# 425AK01A_S09.net
KiCad netlist of a schematic drawn in Altium Designer
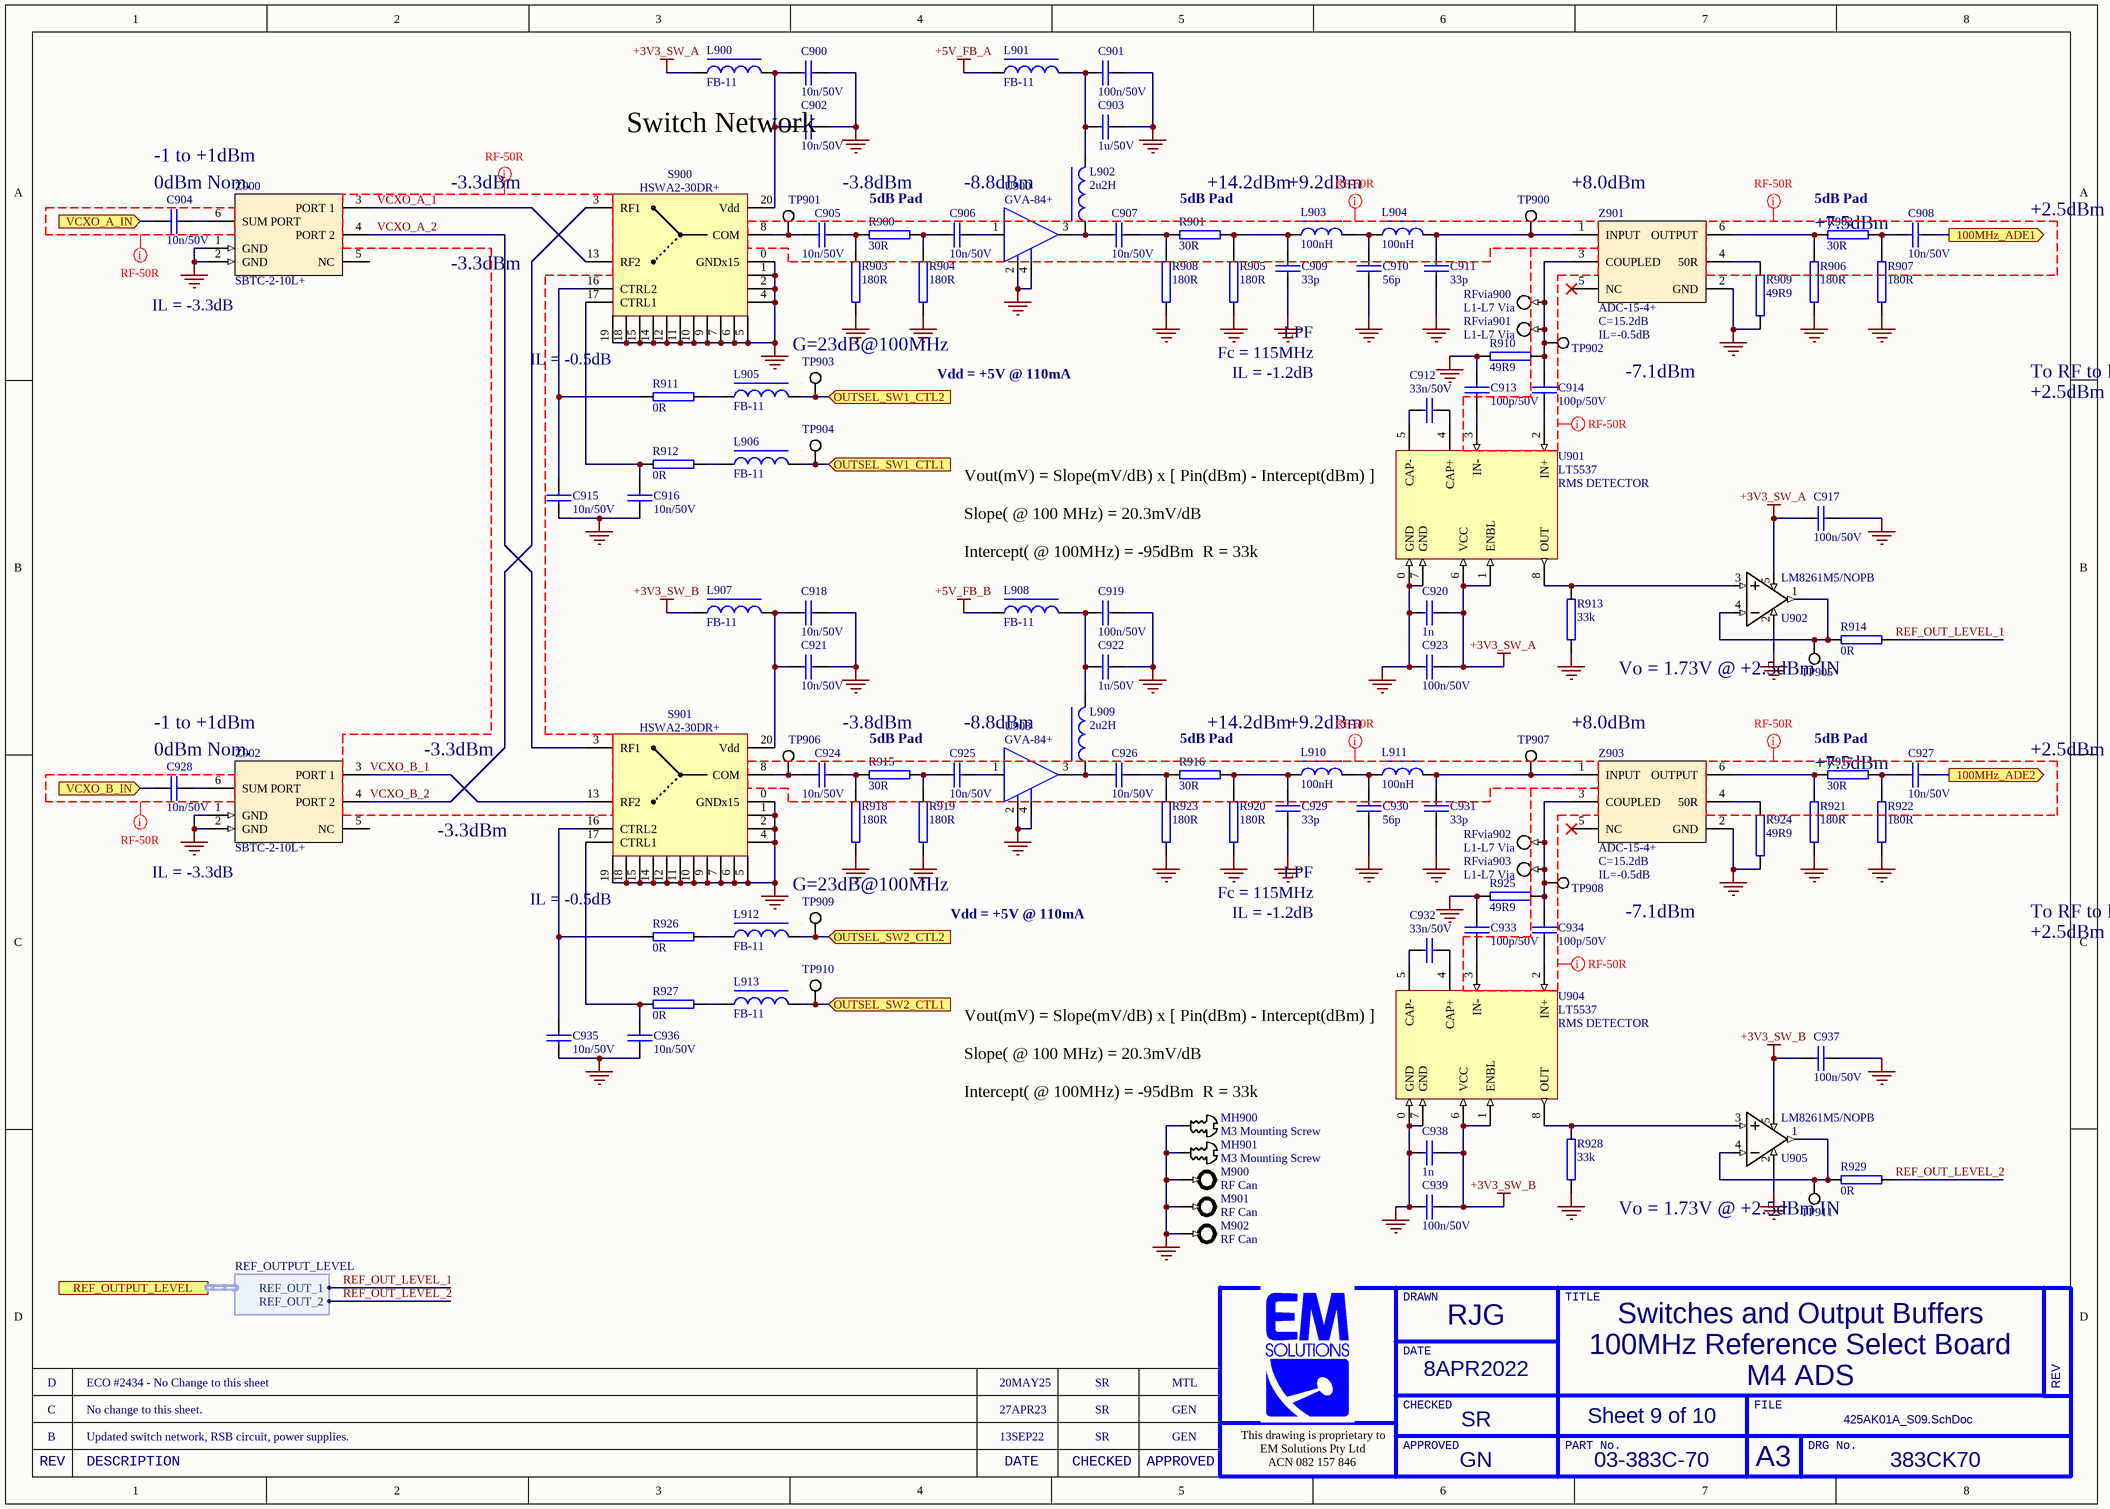
[diagram p0: 425AK01A_S09.SchDoc]

(export (version "E")
  (design (tool "Eeschema 10.0.6"))
  (components
    (comp (ref "C900")
      (value "10n/50V")
      (footprint "0402C")
      (description "Capacitor, 0402, 10n X7R 10% 50V Ceramic, NiSn")
      (fields (field (name "PART NUMBER") "41-010N-12") (field (name "MANUFACTURER") "MURATA"))
      (libsource (lib "EM DFM Library") (part "CAP"))
    )
    (comp (ref "C901")
      (value "100n/50V")
      (footprint "0402C")
      (description "Capacitor, 0402, 100n, X7R, 10% 50V, Ceramic")
      (fields (field (name "PART NUMBER") "41-100N-13") (field (name "MANUFACTURER") "MURATA"))
      (libsource (lib "EM DFM Library") (part "CAP"))
    )
    (comp (ref "C902")
      (value "10n/50V")
      (footprint "0402C")
      (description "Capacitor, 0402, 10n X7R 10% 50V Ceramic, NiSn")
      (fields (field (name "PART NUMBER") "41-010N-12") (field (name "MANUFACTURER") "MURATA"))
      (libsource (lib "EM DFM Library") (part "CAP"))
    )
    (comp (ref "C903")
      (value "1u/50V")
      (footprint "0603C")
      (description "Capacitor, 0603, 1u X7R 10% 50V Ceramic, NiSn")
      (fields (field (name "PART NUMBER") "41-01U0-06") (field (name "MANUFACTURER") "TAIYOYUDEN"))
      (libsource (lib "EM DFM Library") (part "CAP"))
    )
    (comp (ref "C904")
      (value "10n/50V")
      (footprint "0402C")
      (description "Capacitor, 0402, 10n X7R 10% 50V Ceramic, NiSn")
      (fields (field (name "PART NUMBER") "41-010N-12") (field (name "MANUFACTURER") "MURATA"))
      (libsource (lib "EM DFM Library") (part "CAP"))
    )
    (comp (ref "C905")
      (value "10n/50V")
      (footprint "0402C")
      (description "Capacitor, 0402, 10n X7R 10% 50V Ceramic, NiSn")
      (fields (field (name "PART NUMBER") "41-010N-12") (field (name "MANUFACTURER") "MURATA"))
      (libsource (lib "EM DFM Library") (part "CAP"))
    )
    (comp (ref "C906")
      (value "10n/50V")
      (footprint "0402C")
      (description "Capacitor, 0402, 10n X7R 10% 50V Ceramic, NiSn")
      (fields (field (name "PART NUMBER") "41-010N-12") (field (name "MANUFACTURER") "MURATA"))
      (libsource (lib "EM DFM Library") (part "CAP"))
    )
    (comp (ref "C907")
      (value "10n/50V")
      (footprint "0402C")
      (description "Capacitor, 0402, 10n X7R 10% 50V Ceramic, NiSn")
      (fields (field (name "PART NUMBER") "41-010N-12") (field (name "MANUFACTURER") "MURATA"))
      (libsource (lib "EM DFM Library") (part "CAP"))
    )
    (comp (ref "C908")
      (value "10n/50V")
      (footprint "0402C")
      (description "Capacitor, 0402, 10n X7R 10% 50V Ceramic, NiSn")
      (fields (field (name "PART NUMBER") "41-010N-12") (field (name "MANUFACTURER") "MURATA"))
      (libsource (lib "EM DFM Library") (part "CAP"))
    )
    (comp (ref "C909")
      (value "33p")
      (footprint "0402C")
      (description "Capacitor, 0402, 33p NPO 2% 50V HiQ, NiSn")
      (fields (field (name "PART NUMBER") "41-033P-10") (field (name "MANUFACTURER") "MURATA"))
      (libsource (lib "EM DFM Library") (part "CAP"))
    )
    (comp (ref "C910")
      (value "56p")
      (footprint "0402C")
      (description "Capacitor, 0402, 56p NPO 5% 50V Ceramic, NiSn")
      (fields (field (name "PART NUMBER") "41-056P-05") (field (name "MANUFACTURER") "YAGEO"))
      (libsource (lib "EM DFM Library") (part "CAP"))
    )
    (comp (ref "C911")
      (value "33p")
      (footprint "0402C")
      (description "Capacitor, 0402, 33p NPO 2% 50V HiQ, NiSn")
      (fields (field (name "PART NUMBER") "41-033P-10") (field (name "MANUFACTURER") "MURATA"))
      (libsource (lib "EM DFM Library") (part "CAP"))
    )
    (comp (ref "C912")
      (value "33n/50V")
      (footprint "0402C")
      (description "*Capacitor, 0402, 33n, X7R, 10%, 50V")
      (fields (field (name "PART NUMBER") "41-033N-01"))
      (libsource (lib "Russell") (part "41-033N-01"))
    )
    (comp (ref "C913")
      (value "100p/50V")
      (footprint "0402C")
      (description "Capacitor, 0402, 100p NPO 5% 50V Ceramic, AEC-Q200")
      (fields (field (name "PART NUMBER") "41-100P-11") (field (name "MANUFACTURER") "TDK"))
      (libsource (lib "EM DFM Library") (part "CAP"))
    )
    (comp (ref "C914")
      (value "100p/50V")
      (footprint "0402C")
      (description "Capacitor, 0402, 100p NPO 5% 50V Ceramic, AEC-Q200")
      (fields (field (name "PART NUMBER") "41-100P-11") (field (name "MANUFACTURER") "TDK"))
      (libsource (lib "EM DFM Library") (part "CAP"))
    )
    (comp (ref "C915")
      (value "10n/50V")
      (footprint "0402C")
      (description "Capacitor, 0402, 10n X7R 10% 50V Ceramic, NiSn")
      (fields (field (name "PART NUMBER") "41-010N-12") (field (name "MANUFACTURER") "MURATA"))
      (libsource (lib "EM DFM Library") (part "CAP"))
    )
    (comp (ref "C916")
      (value "10n/50V")
      (footprint "0402C")
      (description "Capacitor, 0402, 10n X7R 10% 50V Ceramic, NiSn")
      (fields (field (name "PART NUMBER") "41-010N-12") (field (name "MANUFACTURER") "MURATA"))
      (libsource (lib "EM DFM Library") (part "CAP"))
    )
    (comp (ref "C917")
      (value "100n/50V")
      (footprint "0402C")
      (description "Capacitor, 0402, 100n, X7R, 10% 50V, Ceramic")
      (fields (field (name "PART NUMBER") "41-100N-13") (field (name "MANUFACTURER") "MURATA"))
      (libsource (lib "EM DFM Library") (part "CAP"))
    )
    (comp (ref "C918")
      (value "10n/50V")
      (footprint "0402C")
      (description "Capacitor, 0402, 10n X7R 10% 50V Ceramic, NiSn")
      (fields (field (name "PART NUMBER") "41-010N-12") (field (name "MANUFACTURER") "MURATA"))
      (libsource (lib "EM DFM Library") (part "CAP"))
    )
    (comp (ref "C919")
      (value "100n/50V")
      (footprint "0402C")
      (description "Capacitor, 0402, 100n, X7R, 10% 50V, Ceramic")
      (fields (field (name "PART NUMBER") "41-100N-13") (field (name "MANUFACTURER") "MURATA"))
      (libsource (lib "EM DFM Library") (part "CAP"))
    )
    (comp (ref "C920")
      (value "1n")
      (footprint "0402C")
      (description "Capacitor, 0402, 1n X7R 10% 50V Ceramic, NiSn")
      (fields (field (name "PART NUMBER") "41-01N0-05"))
      (libsource (lib "Russell") (part "1n_50V_0402"))
    )
    (comp (ref "C921")
      (value "10n/50V")
      (footprint "0402C")
      (description "Capacitor, 0402, 10n X7R 10% 50V Ceramic, NiSn")
      (fields (field (name "PART NUMBER") "41-010N-12") (field (name "MANUFACTURER") "MURATA"))
      (libsource (lib "EM DFM Library") (part "CAP"))
    )
    (comp (ref "C922")
      (value "1u/50V")
      (footprint "0603C")
      (description "Capacitor, 0603, 1u X7R 10% 50V Ceramic, NiSn")
      (fields (field (name "PART NUMBER") "41-01U0-06") (field (name "MANUFACTURER") "TAIYOYUDEN"))
      (libsource (lib "EM DFM Library") (part "CAP"))
    )
    (comp (ref "C923")
      (value "100n/50V")
      (footprint "0402C")
      (description "Capacitor, 0402, 100n, X7R, 10% 50V, Ceramic")
      (fields (field (name "PART NUMBER") "41-100N-13") (field (name "MANUFACTURER") "MURATA"))
      (libsource (lib "EM DFM Library") (part "CAP"))
    )
    (comp (ref "C924")
      (value "10n/50V")
      (footprint "0402C")
      (description "Capacitor, 0402, 10n X7R 10% 50V Ceramic, NiSn")
      (fields (field (name "PART NUMBER") "41-010N-12") (field (name "MANUFACTURER") "MURATA"))
      (libsource (lib "EM DFM Library") (part "CAP"))
    )
    (comp (ref "C925")
      (value "10n/50V")
      (footprint "0402C")
      (description "Capacitor, 0402, 10n X7R 10% 50V Ceramic, NiSn")
      (fields (field (name "PART NUMBER") "41-010N-12") (field (name "MANUFACTURER") "MURATA"))
      (libsource (lib "EM DFM Library") (part "CAP"))
    )
    (comp (ref "C926")
      (value "10n/50V")
      (footprint "0402C")
      (description "Capacitor, 0402, 10n X7R 10% 50V Ceramic, NiSn")
      (fields (field (name "PART NUMBER") "41-010N-12") (field (name "MANUFACTURER") "MURATA"))
      (libsource (lib "EM DFM Library") (part "CAP"))
    )
    (comp (ref "C927")
      (value "10n/50V")
      (footprint "0402C")
      (description "Capacitor, 0402, 10n X7R 10% 50V Ceramic, NiSn")
      (fields (field (name "PART NUMBER") "41-010N-12") (field (name "MANUFACTURER") "MURATA"))
      (libsource (lib "EM DFM Library") (part "CAP"))
    )
    (comp (ref "C928")
      (value "10n/50V")
      (footprint "0402C")
      (description "Capacitor, 0402, 10n X7R 10% 50V Ceramic, NiSn")
      (fields (field (name "PART NUMBER") "41-010N-12") (field (name "MANUFACTURER") "MURATA"))
      (libsource (lib "EM DFM Library") (part "CAP"))
    )
    (comp (ref "C929")
      (value "33p")
      (footprint "0402C")
      (description "Capacitor, 0402, 33p NPO 2% 50V HiQ, NiSn")
      (fields (field (name "PART NUMBER") "41-033P-10") (field (name "MANUFACTURER") "MURATA"))
      (libsource (lib "EM DFM Library") (part "CAP"))
    )
    (comp (ref "C930")
      (value "56p")
      (footprint "0402C")
      (description "Capacitor, 0402, 56p NPO 5% 50V Ceramic, NiSn")
      (fields (field (name "PART NUMBER") "41-056P-05") (field (name "MANUFACTURER") "YAGEO"))
      (libsource (lib "EM DFM Library") (part "CAP"))
    )
    (comp (ref "C931")
      (value "33p")
      (footprint "0402C")
      (description "Capacitor, 0402, 33p NPO 2% 50V HiQ, NiSn")
      (fields (field (name "PART NUMBER") "41-033P-10") (field (name "MANUFACTURER") "MURATA"))
      (libsource (lib "EM DFM Library") (part "CAP"))
    )
    (comp (ref "C932")
      (value "33n/50V")
      (footprint "0402C")
      (description "*Capacitor, 0402, 33n, X7R, 10%, 50V")
      (fields (field (name "PART NUMBER") "41-033N-01"))
      (libsource (lib "Russell") (part "41-033N-01"))
    )
    (comp (ref "C933")
      (value "100p/50V")
      (footprint "0402C")
      (description "Capacitor, 0402, 100p NPO 5% 50V Ceramic, AEC-Q200")
      (fields (field (name "PART NUMBER") "41-100P-11") (field (name "MANUFACTURER") "TDK"))
      (libsource (lib "EM DFM Library") (part "CAP"))
    )
    (comp (ref "C934")
      (value "100p/50V")
      (footprint "0402C")
      (description "Capacitor, 0402, 100p NPO 5% 50V Ceramic, AEC-Q200")
      (fields (field (name "PART NUMBER") "41-100P-11") (field (name "MANUFACTURER") "TDK"))
      (libsource (lib "EM DFM Library") (part "CAP"))
    )
    (comp (ref "C935")
      (value "10n/50V")
      (footprint "0402C")
      (description "Capacitor, 0402, 10n X7R 10% 50V Ceramic, NiSn")
      (fields (field (name "PART NUMBER") "41-010N-12") (field (name "MANUFACTURER") "MURATA"))
      (libsource (lib "EM DFM Library") (part "CAP"))
    )
    (comp (ref "C936")
      (value "10n/50V")
      (footprint "0402C")
      (description "Capacitor, 0402, 10n X7R 10% 50V Ceramic, NiSn")
      (fields (field (name "PART NUMBER") "41-010N-12") (field (name "MANUFACTURER") "MURATA"))
      (libsource (lib "EM DFM Library") (part "CAP"))
    )
    (comp (ref "C937")
      (value "100n/50V")
      (footprint "0402C")
      (description "Capacitor, 0402, 100n, X7R, 10% 50V, Ceramic")
      (fields (field (name "PART NUMBER") "41-100N-13") (field (name "MANUFACTURER") "MURATA"))
      (libsource (lib "EM DFM Library") (part "CAP"))
    )
    (comp (ref "C938")
      (value "1n")
      (footprint "0402C")
      (description "Capacitor, 0402, 1n X7R 10% 50V Ceramic, NiSn")
      (fields (field (name "PART NUMBER") "41-01N0-05"))
      (libsource (lib "Russell") (part "1n_50V_0402"))
    )
    (comp (ref "C939")
      (value "100n/50V")
      (footprint "0402C")
      (description "Capacitor, 0402, 100n, X7R, 10% 50V, Ceramic")
      (fields (field (name "PART NUMBER") "41-100N-13") (field (name "MANUFACTURER") "MURATA"))
      (libsource (lib "EM DFM Library") (part "CAP"))
    )
    (comp (ref "L900")
      (value "FB-11")
      (footprint "0402L")
      (description "Solid Inductor, 600ohm@100MHz, DCR=0.52, 0.3A, 0402 size")
      (fields (field (name "PART NUMBER") "46-B-11") (field (name "MANUFACTURER") "TDK"))
      (libsource (lib "EM DFM Library") (part "IND"))
    )
    (comp (ref "L901")
      (value "FB-11")
      (footprint "0402L")
      (description "Solid Inductor, 600ohm@100MHz, DCR=0.52, 0.3A, 0402 size")
      (fields (field (name "PART NUMBER") "46-B-11") (field (name "MANUFACTURER") "TDK"))
      (libsource (lib "") (part "IND_1"))
    )
    (comp (ref "L902")
      (value "2u2H")
      (footprint "0805L")
      (description "Inductor, Chip, 2u2H 10%, 0805, SIMID08B Series")
      (fields (field (name "PART NUMBER") "46-02U2-01") (field (name "MANUFACTURER") "SIEMENS"))
      (libsource (lib "") (part "IND_1"))
    )
    (comp (ref "L903")
      (value "100nH")
      (footprint "0402L")
      (description "Inductor, Chip, 100nH, 0402")
      (fields (field (name "PART NUMBER") "46-100N-03"))
      (libsource (lib "Russell") (part "46-100N-03"))
    )
    (comp (ref "L904")
      (value "100nH")
      (footprint "0402L")
      (description "Inductor, Chip, 100nH, 0402")
      (fields (field (name "PART NUMBER") "46-100N-03"))
      (libsource (lib "Russell") (part "46-100N-03"))
    )
    (comp (ref "L905")
      (value "FB-11")
      (footprint "0402L")
      (description "Solid Inductor, 600ohm@100MHz, DCR=0.52, 0.3A, 0402 size")
      (fields (field (name "PART NUMBER") "46-B-11") (field (name "MANUFACTURER") "TDK"))
      (libsource (lib "EM DFM Library") (part "IND"))
    )
    (comp (ref "L906")
      (value "FB-11")
      (footprint "0402L")
      (description "Solid Inductor, 600ohm@100MHz, DCR=0.52, 0.3A, 0402 size")
      (fields (field (name "PART NUMBER") "46-B-11") (field (name "MANUFACTURER") "TDK"))
      (libsource (lib "EM DFM Library") (part "IND"))
    )
    (comp (ref "L907")
      (value "FB-11")
      (footprint "0402L")
      (description "Solid Inductor, 600ohm@100MHz, DCR=0.52, 0.3A, 0402 size")
      (fields (field (name "PART NUMBER") "46-B-11") (field (name "MANUFACTURER") "TDK"))
      (libsource (lib "EM DFM Library") (part "IND"))
    )
    (comp (ref "L908")
      (value "FB-11")
      (footprint "0402L")
      (description "Solid Inductor, 600ohm@100MHz, DCR=0.52, 0.3A, 0402 size")
      (fields (field (name "PART NUMBER") "46-B-11") (field (name "MANUFACTURER") "TDK"))
      (libsource (lib "") (part "IND_1"))
    )
    (comp (ref "L909")
      (value "2u2H")
      (footprint "0805L")
      (description "Inductor, Chip, 2u2H 10%, 0805, SIMID08B Series")
      (fields (field (name "PART NUMBER") "46-02U2-01") (field (name "MANUFACTURER") "SIEMENS"))
      (libsource (lib "") (part "IND_1"))
    )
    (comp (ref "L910")
      (value "100nH")
      (footprint "0402L")
      (description "Inductor, Chip, 100nH, 0402")
      (fields (field (name "PART NUMBER") "46-100N-03"))
      (libsource (lib "Russell") (part "46-100N-03"))
    )
    (comp (ref "L911")
      (value "100nH")
      (footprint "0402L")
      (description "Inductor, Chip, 100nH, 0402")
      (fields (field (name "PART NUMBER") "46-100N-03"))
      (libsource (lib "Russell") (part "46-100N-03"))
    )
    (comp (ref "L912")
      (value "FB-11")
      (footprint "0402L")
      (description "Solid Inductor, 600ohm@100MHz, DCR=0.52, 0.3A, 0402 size")
      (fields (field (name "PART NUMBER") "46-B-11") (field (name "MANUFACTURER") "TDK"))
      (libsource (lib "EM DFM Library") (part "IND"))
    )
    (comp (ref "L913")
      (value "FB-11")
      (footprint "0402L")
      (description "Solid Inductor, 600ohm@100MHz, DCR=0.52, 0.3A, 0402 size")
      (fields (field (name "PART NUMBER") "46-B-11") (field (name "MANUFACTURER") "TDK"))
      (libsource (lib "EM DFM Library") (part "IND"))
    )
    (comp (ref "M900")
      (value "RF Can")
      (footprint "Can_38x25.4x6mm")
      (fields (field (name "PART NUMBER") "11-0256"))
      (libsource (lib "Russell") (part "Can-RF"))
    )
    (comp (ref "M901")
      (value "RF Can")
      (footprint "Can_38x25.4x6mm")
      (fields (field (name "PART NUMBER") "11-0256"))
      (libsource (lib "Russell") (part "Can-RF"))
    )
    (comp (ref "M902")
      (value "RF Can")
      (footprint "Can_38x25.4x6mm")
      (fields (field (name "PART NUMBER") "11-0256"))
      (libsource (lib "Russell") (part "Can-RF"))
    )
    (comp (ref "MH900")
      (value "M3 Mounting Screw")
      (footprint "M3_SCREW")
      (libsource (lib "Russell") (part "M3 Screw"))
    )
    (comp (ref "MH901")
      (value "M3 Mounting Screw")
      (footprint "M3_SCREW")
      (libsource (lib "Russell") (part "M3 Screw"))
    )
    (comp (ref "R900")
      (value "30R")
      (footprint "0402")
      (description "Resistor, 30R, 0402, 1%, 100mW")
      (fields (field (name "PART NUMBER") "44-030R-04"))
      (libsource (lib "Russell") (part "44-030R-04"))
    )
    (comp (ref "R901")
      (value "30R")
      (footprint "0402")
      (description "Resistor, 30R, 0402, 1%, 100mW")
      (fields (field (name "PART NUMBER") "44-030R-04"))
      (libsource (lib "Russell") (part "44-030R-04"))
    )
    (comp (ref "R902")
      (value "30R")
      (footprint "0402")
      (description "Resistor, 30R, 0402, 1%, 100mW")
      (fields (field (name "PART NUMBER") "44-030R-04"))
      (libsource (lib "Russell") (part "44-030R-04"))
    )
    (comp (ref "R903")
      (value "180R")
      (footprint "0402")
      (description "Resistor, 0402, 180R 1% 0.063W")
      (fields (field (name "PART NUMBER") "44-180R-10") (field (name "MANUFACTURER") "GENERIC"))
      (libsource (lib "EM DFM Library") (part "RES"))
    )
    (comp (ref "R904")
      (value "180R")
      (footprint "0402")
      (description "Resistor, 0402, 180R 1% 0.063W")
      (fields (field (name "PART NUMBER") "44-180R-10") (field (name "MANUFACTURER") "GENERIC"))
      (libsource (lib "EM DFM Library") (part "RES"))
    )
    (comp (ref "R905")
      (value "180R")
      (footprint "0402")
      (description "Resistor, 0402, 180R 1% 0.063W")
      (fields (field (name "PART NUMBER") "44-180R-10") (field (name "MANUFACTURER") "GENERIC"))
      (libsource (lib "EM DFM Library") (part "RES"))
    )
    (comp (ref "R906")
      (value "180R")
      (footprint "0402")
      (description "Resistor, 0402, 180R 1% 0.063W")
      (fields (field (name "PART NUMBER") "44-180R-10") (field (name "MANUFACTURER") "GENERIC"))
      (libsource (lib "EM DFM Library") (part "RES"))
    )
    (comp (ref "R907")
      (value "180R")
      (footprint "0402")
      (description "Resistor, 0402, 180R 1% 0.063W")
      (fields (field (name "PART NUMBER") "44-180R-10") (field (name "MANUFACTURER") "GENERIC"))
      (libsource (lib "EM DFM Library") (part "RES"))
    )
    (comp (ref "R908")
      (value "180R")
      (footprint "0402")
      (description "Resistor, 0402, 180R 1% 0.063W")
      (fields (field (name "PART NUMBER") "44-180R-10") (field (name "MANUFACTURER") "GENERIC"))
      (libsource (lib "EM DFM Library") (part "RES"))
    )
    (comp (ref "R909")
      (value "49R9")
      (footprint "0402")
      (description "Resistor, 0402, 49R9 1% 0.063W")
      (fields (field (name "PART NUMBER") "44-049R9-10"))
      (libsource (lib "EM DFM Library") (part "RES"))
    )
    (comp (ref "R910")
      (value "49R9")
      (footprint "0402")
      (description "Resistor, 0402, 49R9 1% 0.063W")
      (fields (field (name "PART NUMBER") "44-049R9-10"))
      (libsource (lib "EM DFM Library") (part "RES"))
    )
    (comp (ref "R911")
      (value "0R")
      (footprint "0402")
      (description "Resistor, 0402, 0R 1% 0.063W")
      (fields (field (name "PART NUMBER") "44-000R-10") (field (name "MANUFACTURER") "GENERIC"))
      (libsource (lib "EM DFM Library") (part "RES"))
    )
    (comp (ref "R912")
      (value "0R")
      (footprint "0402")
      (description "Resistor, 0402, 0R 1% 0.063W")
      (fields (field (name "PART NUMBER") "44-000R-10") (field (name "MANUFACTURER") "GENERIC"))
      (libsource (lib "EM DFM Library") (part "RES"))
    )
    (comp (ref "R913")
      (value "33k")
      (footprint "0402")
      (description "Resistor, 0402, 33k 1% 0.063W")
      (fields (field (name "PART NUMBER") "44-033K-10") (field (name "MANUFACTURER") "GENERIC"))
      (libsource (lib "EM DFM Library") (part "RES"))
    )
    (comp (ref "R914")
      (value "0R")
      (footprint "0402")
      (description "Resistor, 0402, 0R 1% 0.063W")
      (fields (field (name "PART NUMBER") "44-000R-10"))
      (libsource (lib "EM DFM Library") (part "RES"))
    )
    (comp (ref "R915")
      (value "30R")
      (footprint "0402")
      (description "Resistor, 30R, 0402, 1%, 100mW")
      (fields (field (name "PART NUMBER") "44-030R-04"))
      (libsource (lib "Russell") (part "44-030R-04"))
    )
    (comp (ref "R916")
      (value "30R")
      (footprint "0402")
      (description "Resistor, 30R, 0402, 1%, 100mW")
      (fields (field (name "PART NUMBER") "44-030R-04"))
      (libsource (lib "Russell") (part "44-030R-04"))
    )
    (comp (ref "R917")
      (value "30R")
      (footprint "0402")
      (description "Resistor, 30R, 0402, 1%, 100mW")
      (fields (field (name "PART NUMBER") "44-030R-04"))
      (libsource (lib "Russell") (part "44-030R-04"))
    )
    (comp (ref "R918")
      (value "180R")
      (footprint "0402")
      (description "Resistor, 0402, 180R 1% 0.063W")
      (fields (field (name "PART NUMBER") "44-180R-10") (field (name "MANUFACTURER") "GENERIC"))
      (libsource (lib "EM DFM Library") (part "RES"))
    )
    (comp (ref "R919")
      (value "180R")
      (footprint "0402")
      (description "Resistor, 0402, 180R 1% 0.063W")
      (fields (field (name "PART NUMBER") "44-180R-10") (field (name "MANUFACTURER") "GENERIC"))
      (libsource (lib "EM DFM Library") (part "RES"))
    )
    (comp (ref "R920")
      (value "180R")
      (footprint "0402")
      (description "Resistor, 0402, 180R 1% 0.063W")
      (fields (field (name "PART NUMBER") "44-180R-10") (field (name "MANUFACTURER") "GENERIC"))
      (libsource (lib "EM DFM Library") (part "RES"))
    )
    (comp (ref "R921")
      (value "180R")
      (footprint "0402")
      (description "Resistor, 0402, 180R 1% 0.063W")
      (fields (field (name "PART NUMBER") "44-180R-10") (field (name "MANUFACTURER") "GENERIC"))
      (libsource (lib "EM DFM Library") (part "RES"))
    )
    (comp (ref "R922")
      (value "180R")
      (footprint "0402")
      (description "Resistor, 0402, 180R 1% 0.063W")
      (fields (field (name "PART NUMBER") "44-180R-10") (field (name "MANUFACTURER") "GENERIC"))
      (libsource (lib "EM DFM Library") (part "RES"))
    )
    (comp (ref "R923")
      (value "180R")
      (footprint "0402")
      (description "Resistor, 0402, 180R 1% 0.063W")
      (fields (field (name "PART NUMBER") "44-180R-10") (field (name "MANUFACTURER") "GENERIC"))
      (libsource (lib "EM DFM Library") (part "RES"))
    )
    (comp (ref "R924")
      (value "49R9")
      (footprint "0402")
      (description "Resistor, 0402, 49R9 1% 0.063W")
      (fields (field (name "PART NUMBER") "44-049R9-10"))
      (libsource (lib "EM DFM Library") (part "RES"))
    )
    (comp (ref "R925")
      (value "49R9")
      (footprint "0402")
      (description "Resistor, 0402, 49R9 1% 0.063W")
      (fields (field (name "PART NUMBER") "44-049R9-10"))
      (libsource (lib "EM DFM Library") (part "RES"))
    )
    (comp (ref "R926")
      (value "0R")
      (footprint "0402")
      (description "Resistor, 0402, 0R 1% 0.063W")
      (fields (field (name "PART NUMBER") "44-000R-10") (field (name "MANUFACTURER") "GENERIC"))
      (libsource (lib "EM DFM Library") (part "RES"))
    )
    (comp (ref "R927")
      (value "0R")
      (footprint "0402")
      (description "Resistor, 0402, 0R 1% 0.063W")
      (fields (field (name "PART NUMBER") "44-000R-10") (field (name "MANUFACTURER") "GENERIC"))
      (libsource (lib "EM DFM Library") (part "RES"))
    )
    (comp (ref "R928")
      (value "33k")
      (footprint "0402")
      (description "Resistor, 0402, 33k 1% 0.063W")
      (fields (field (name "PART NUMBER") "44-033K-10") (field (name "MANUFACTURER") "GENERIC"))
      (libsource (lib "EM DFM Library") (part "RES"))
    )
    (comp (ref "R929")
      (value "0R")
      (footprint "0402")
      (description "Resistor, 0402, 0R 1% 0.063W")
      (fields (field (name "PART NUMBER") "44-000R-10"))
      (libsource (lib "EM DFM Library") (part "RES"))
    )
    (comp (ref "RFvia900")
      (value "L1-L7 Via")
      (footprint "RFvia_L1-L7")
      (description "RF Via from layer 1 to layer 7, on an 8-layer board.")
      (libsource (lib "RFvias-8layer") (part "RFvia_L1-L7"))
    )
    (comp (ref "RFvia901")
      (value "L1-L7 Via")
      (footprint "RFvia_L1-L7")
      (description "RF Via from layer 1 to layer 7, on an 8-layer board.")
      (libsource (lib "RFvias-8layer") (part "RFvia_L1-L7"))
    )
    (comp (ref "RFvia902")
      (value "L1-L7 Via")
      (footprint "RFvia_L1-L7")
      (description "RF Via from layer 1 to layer 7, on an 8-layer board.")
      (libsource (lib "RFvias-8layer") (part "RFvia_L1-L7"))
    )
    (comp (ref "RFvia903")
      (value "L1-L7 Via")
      (footprint "RFvia_L1-L7")
      (description "RF Via from layer 1 to layer 7, on an 8-layer board.")
      (libsource (lib "RFvias-8layer") (part "RFvia_L1-L7"))
    )
    (comp (ref "S900")
      (value "HSWA2-30DR+")
      (footprint "DG983-1")
      (description "RF Switch, SPDT, DC-3GHz, Absorptive, IL=1dB, I=60dB, P=30dBm, 2V7-3V3, 4x4 QFN")
      (fields (field (name "PART NUMBER") "54-30-01") (field (name "MANUFACTURER") "MINICCTS"))
      (libsource (lib "Russell") (part "HSWA2-30DR+"))
    )
    (comp (ref "S901")
      (value "HSWA2-30DR+")
      (footprint "DG983-1")
      (description "RF Switch, SPDT, DC-3GHz, Absorptive, IL=1dB, I=60dB, P=30dBm, 2V7-3V3, 4x4 QFN")
      (fields (field (name "PART NUMBER") "54-30-01") (field (name "MANUFACTURER") "MINICCTS"))
      (libsource (lib "Russell") (part "HSWA2-30DR+"))
    )
    (comp (ref "TP900")
      (value "Pad")
      (footprint "Testpoint-0.5mm-SMT-withPaste")
      (description "Pad that can be a test point or a hot via")
      (libsource (lib "Russell") (part "Pad"))
    )
    (comp (ref "TP901")
      (value "Pad")
      (footprint "Testpoint-0.5mm-SMT-withPaste")
      (description "Pad that can be a test point or a hot via")
      (libsource (lib "Russell") (part "Pad"))
    )
    (comp (ref "TP902")
      (value "Pad")
      (footprint "Testpoint-0.5mm-SMT-withPaste")
      (description "Pad that can be a test point or a hot via")
      (libsource (lib "Russell") (part "Pad"))
    )
    (comp (ref "TP903")
      (value "Pad")
      (footprint "Testpoint-0.5mm-SMT-withPaste")
      (description "Pad that can be a test point or a hot via")
      (libsource (lib "Russell") (part "Pad"))
    )
    (comp (ref "TP904")
      (value "Pad")
      (footprint "Testpoint-0.5mm-SMT-withPaste")
      (description "Pad that can be a test point or a hot via")
      (libsource (lib "Russell") (part "Pad"))
    )
    (comp (ref "TP905")
      (value "Pad")
      (footprint "Testpoint-0.5mm-SMT-withPaste")
      (description "Pad that can be a test point or a hot via")
      (libsource (lib "Russell") (part "Pad"))
    )
    (comp (ref "TP906")
      (value "Pad")
      (footprint "Testpoint-0.5mm-SMT-withPaste")
      (description "Pad that can be a test point or a hot via")
      (libsource (lib "Russell") (part "Pad"))
    )
    (comp (ref "TP907")
      (value "Pad")
      (footprint "Testpoint-0.5mm-SMT-withPaste")
      (description "Pad that can be a test point or a hot via")
      (libsource (lib "Russell") (part "Pad"))
    )
    (comp (ref "TP908")
      (value "Pad")
      (footprint "Testpoint-0.5mm-SMT-withPaste")
      (description "Pad that can be a test point or a hot via")
      (libsource (lib "Russell") (part "Pad"))
    )
    (comp (ref "TP909")
      (value "Pad")
      (footprint "Testpoint-0.5mm-SMT-withPaste")
      (description "Pad that can be a test point or a hot via")
      (libsource (lib "Russell") (part "Pad"))
    )
    (comp (ref "TP910")
      (value "Pad")
      (footprint "Testpoint-0.5mm-SMT-withPaste")
      (description "Pad that can be a test point or a hot via")
      (libsource (lib "Russell") (part "Pad"))
    )
    (comp (ref "TP911")
      (value "Pad")
      (footprint "Testpoint-0.5mm-SMT-withPaste")
      (description "Pad that can be a test point or a hot via")
      (libsource (lib "Russell") (part "Pad"))
    )
    (comp (ref "U900")
      (value "GVA-84+")
      (footprint "SOT-89-RF")
      (description "MMIC, DC-7GHz, G=24dB, P1dB=20.5dBm, SOT-89")
      (fields (field (name "PART NUMBER") "58-GVA84-01"))
      (libsource (lib "NewMediator") (part "GVA-84+"))
    )
    (comp (ref "U901")
      (value "LT5537")
      (footprint "DFN-8")
      (description "RF Detector, 10-1000MHz, 83dB, -40/+85C, 8-DFN 3x2mm")
      (fields (field (name "MPN") "LT5537EDDB") (field (name "PART NUMBER") "54-5537-01"))
      (libsource (lib "Russell") (part "LT5537EDDB"))
    )
    (comp (ref "U902")
      (value "LM8261M5/NOPB")
      (footprint "SOT-23/5")
      (description "Opamp, RRIO, 2V5 to 30V supply, 21MHz GBWP")
      (fields (field (name "PART NUMBER") "52-8621-01"))
      (libsource (lib "Russell") (part "OpAmp-LM8261"))
    )
    (comp (ref "U903")
      (value "GVA-84+")
      (footprint "SOT-89-RF")
      (description "MMIC, DC-7GHz, G=24dB, P1dB=20.5dBm, SOT-89")
      (fields (field (name "PART NUMBER") "58-GVA84-01"))
      (libsource (lib "NewMediator") (part "GVA-84+"))
    )
    (comp (ref "U904")
      (value "LT5537")
      (footprint "DFN-8")
      (description "RF Detector, 10-1000MHz, 83dB, -40/+85C, 8-DFN 3x2mm")
      (fields (field (name "MPN") "LT5537EDDB") (field (name "PART NUMBER") "54-5537-01"))
      (libsource (lib "Russell") (part "LT5537EDDB"))
    )
    (comp (ref "U905")
      (value "LM8261M5/NOPB")
      (footprint "SOT-23/5")
      (description "Opamp, RRIO, 2V5 to 30V supply, 21MHz GBWP")
      (fields (field (name "PART NUMBER") "52-8621-01"))
      (libsource (lib "Russell") (part "OpAmp-LM8261"))
    )
    (comp (ref "Z900")
      (value "SBTC-2-10L+")
      (footprint "SBTC-2-10L+")
      (description "Divider/Combiner, 2 Way, 0 deg, 10 -1000MHz, Tx Line Tranformer")
      (fields (field (name "PART NUMBER") "33-0055") (field (name "MANUFACTURER") "MINICCTS"))
      (libsource (lib "EM DFM Library") (part "SBTC-2-10L+"))
    )
    (comp (ref "Z901")
      (value "ADC-15-4+")
      (footprint "ADC-15-4+")
      (description "Directional Coupler, C=15.5dB, 5-1000MHz, SM")
      (fields (field (name "PART NUMBER") "33-0058") (field (name "MANUFACTURER") "MINICCTS"))
      (libsource (lib "EM DFM Library") (part "ADC-15-4+"))
    )
    (comp (ref "Z902")
      (value "SBTC-2-10L+")
      (footprint "SBTC-2-10L+")
      (description "Divider/Combiner, 2 Way, 0 deg, 10 -1000MHz, Tx Line Tranformer")
      (fields (field (name "PART NUMBER") "33-0055") (field (name "MANUFACTURER") "MINICCTS"))
      (libsource (lib "EM DFM Library") (part "SBTC-2-10L+"))
    )
    (comp (ref "Z903")
      (value "ADC-15-4+")
      (footprint "ADC-15-4+")
      (description "Directional Coupler, C=15.5dB, 5-1000MHz, SM")
      (fields (field (name "PART NUMBER") "33-0058") (field (name "MANUFACTURER") "MINICCTS"))
      (libsource (lib "EM DFM Library") (part "ADC-15-4+"))
    )
  )
  (nets
    (net (code "2") (name "+3V3_SW_A") (class "Default")
      (node (ref "C917") (pin "1") (pintype "passive"))
      (node (ref "C920") (pin "2") (pintype "passive"))
      (node (ref "C923") (pin "1") (pintype "passive"))
      (node (ref "L900") (pin "2") (pinfunction "2_2") (pintype "passive"))
      (node (ref "U901") (pin "1") (pinfunction "ENBL_1") (pintype "input"))
      (node (ref "U901") (pin "6") (pinfunction "VCC_6") (pintype "input"))
      (node (ref "U902") (pin "5") (pinfunction "V+_5") (pintype "input"))
    )
    (net (code "3") (name "+3V3_SW_B") (class "Default")
      (node (ref "C937") (pin "1") (pintype "passive"))
      (node (ref "C938") (pin "2") (pintype "passive"))
      (node (ref "C939") (pin "1") (pintype "passive"))
      (node (ref "L907") (pin "2") (pinfunction "2_2") (pintype "passive"))
      (node (ref "U904") (pin "1") (pinfunction "ENBL_1") (pintype "input"))
      (node (ref "U904") (pin "6") (pinfunction "VCC_6") (pintype "input"))
      (node (ref "U905") (pin "5") (pinfunction "V+_5") (pintype "input"))
    )
    (net (code "4") (name "+5V_FB_A") (class "Default")
      (node (ref "L901") (pin "1") (pinfunction "1_1") (pintype "passive"))
    )
    (net (code "5") (name "+5V_FB_B") (class "Default")
      (node (ref "L908") (pin "1") (pinfunction "1_1") (pintype "passive"))
    )
    (net (code "6") (name "/100MHz_ADE1") (class "Default") (node (ref "C908") (pin "2") (pintype "passive")))
    (net (code "7") (name "/100MHz_ADE2") (class "Default") (node (ref "C927") (pin "2") (pintype "passive")))
    (net (code "8") (name "/OUTSEL_SW1_CTL1") (class "Default")
      (node (ref "L906") (pin "1") (pinfunction "1_1") (pintype "passive"))
      (node (ref "TP904") (pin "1") (pinfunction "1_1") (pintype "passive"))
    )
    (net (code "9") (name "/OUTSEL_SW1_CTL2") (class "Default")
      (node (ref "L905") (pin "1") (pinfunction "1_1") (pintype "passive"))
      (node (ref "TP903") (pin "1") (pinfunction "1_1") (pintype "passive"))
    )
    (net (code "10") (name "/OUTSEL_SW2_CTL1") (class "Default")
      (node (ref "L913") (pin "1") (pinfunction "1_1") (pintype "passive"))
      (node (ref "TP910") (pin "1") (pinfunction "1_1") (pintype "passive"))
    )
    (net (code "11") (name "/OUTSEL_SW2_CTL2") (class "Default")
      (node (ref "L912") (pin "1") (pinfunction "1_1") (pintype "passive"))
      (node (ref "TP909") (pin "1") (pinfunction "1_1") (pintype "passive"))
    )
    (net (code "12") (name "/REF_OUT_LEVEL_1") (class "Default")
      (node (ref "R914") (pin "2") (pintype "passive"))
    )
    (net (code "13") (name "/REF_OUT_LEVEL_2") (class "Default")
      (node (ref "R929") (pin "2") (pintype "passive"))
    )
    (net (code "14") (name "/VCXO_A_1") (class "Default")
      (node (ref "S900") (pin "13") (pinfunction "RF2_13") (pintype "passive"))
      (node (ref "Z900") (pin "3") (pinfunction "PORT_1_3") (pintype "passive"))
    )
    (net (code "15") (name "/VCXO_A_2") (class "Default")
      (node (ref "S901") (pin "3") (pinfunction "RF1_3") (pintype "passive"))
      (node (ref "Z900") (pin "4") (pinfunction "PORT_2_4") (pintype "passive"))
    )
    (net (code "16") (name "/VCXO_A_IN") (class "Default") (node (ref "C904") (pin "1") (pintype "passive")))
    (net (code "17") (name "/VCXO_B_1") (class "Default")
      (node (ref "S901") (pin "13") (pinfunction "RF2_13") (pintype "passive"))
      (node (ref "Z902") (pin "3") (pinfunction "PORT_1_3") (pintype "passive"))
    )
    (net (code "18") (name "/VCXO_B_2") (class "Default")
      (node (ref "S900") (pin "3") (pinfunction "RF1_3") (pintype "passive"))
      (node (ref "Z902") (pin "4") (pinfunction "PORT_2_4") (pintype "passive"))
    )
    (net (code "19") (name "/VCXO_B_IN") (class "Default") (node (ref "C928") (pin "1") (pintype "passive")))
    (net (code "21") (name "GND") (class "Default")
      (node (ref "C900") (pin "1") (pintype "passive"))
      (node (ref "C901") (pin "2") (pintype "passive"))
      (node (ref "C902") (pin "2") (pintype "passive"))
      (node (ref "C903") (pin "1") (pintype "passive"))
      (node (ref "C909") (pin "2") (pintype "passive"))
      (node (ref "C910") (pin "2") (pintype "passive"))
      (node (ref "C911") (pin "1") (pintype "passive"))
      (node (ref "C913") (pin "1") (pintype "passive"))
      (node (ref "C915") (pin "1") (pintype "passive"))
      (node (ref "C916") (pin "1") (pintype "passive"))
      (node (ref "C917") (pin "2") (pintype "passive"))
      (node (ref "C918") (pin "1") (pintype "passive"))
      (node (ref "C919") (pin "2") (pintype "passive"))
      (node (ref "C920") (pin "1") (pintype "passive"))
      (node (ref "C921") (pin "2") (pintype "passive"))
      (node (ref "C922") (pin "1") (pintype "passive"))
      (node (ref "C923") (pin "2") (pintype "passive"))
      (node (ref "C929") (pin "2") (pintype "passive"))
      (node (ref "C930") (pin "2") (pintype "passive"))
      (node (ref "C931") (pin "1") (pintype "passive"))
      (node (ref "C933") (pin "1") (pintype "passive"))
      (node (ref "C935") (pin "1") (pintype "passive"))
      (node (ref "C936") (pin "1") (pintype "passive"))
      (node (ref "C937") (pin "2") (pintype "passive"))
      (node (ref "C938") (pin "1") (pintype "passive"))
      (node (ref "C939") (pin "2") (pintype "passive"))
      (node (ref "M900") (pin "0") (pinfunction "0_0") (pintype "input"))
      (node (ref "M901") (pin "0") (pinfunction "0_0") (pintype "input"))
      (node (ref "M902") (pin "0") (pinfunction "0_0") (pintype "input"))
      (node (ref "MH900") (pin "1") (pinfunction "1_1") (pintype "passive"))
      (node (ref "MH901") (pin "1") (pinfunction "1_1") (pintype "passive"))
      (node (ref "R903") (pin "1") (pintype "passive"))
      (node (ref "R904") (pin "1") (pintype "passive"))
      (node (ref "R905") (pin "1") (pintype "passive"))
      (node (ref "R906") (pin "1") (pintype "passive"))
      (node (ref "R907") (pin "1") (pintype "passive"))
      (node (ref "R908") (pin "1") (pintype "passive"))
      (node (ref "R909") (pin "1") (pintype "passive"))
      (node (ref "R910") (pin "1") (pintype "passive"))
      (node (ref "R913") (pin "1") (pintype "passive"))
      (node (ref "R918") (pin "1") (pintype "passive"))
      (node (ref "R919") (pin "1") (pintype "passive"))
      (node (ref "R920") (pin "1") (pintype "passive"))
      (node (ref "R921") (pin "1") (pintype "passive"))
      (node (ref "R922") (pin "1") (pintype "passive"))
      (node (ref "R923") (pin "1") (pintype "passive"))
      (node (ref "R924") (pin "1") (pintype "passive"))
      (node (ref "R925") (pin "1") (pintype "passive"))
      (node (ref "R928") (pin "1") (pintype "passive"))
      (node (ref "S900") (pin "0") (pinfunction "GNDx15_0") (pintype "passive"))
      (node (ref "S900") (pin "1") (pinfunction "GND_1") (pintype "passive"))
      (node (ref "S900") (pin "10") (pinfunction "GND_10") (pintype "passive"))
      (node (ref "S900") (pin "11") (pinfunction "GND_11") (pintype "passive"))
      (node (ref "S900") (pin "12") (pinfunction "GND_12") (pintype "passive"))
      (node (ref "S900") (pin "14") (pinfunction "GND_14") (pintype "passive"))
      (node (ref "S900") (pin "15") (pinfunction "GND_15") (pintype "passive"))
      (node (ref "S900") (pin "18") (pinfunction "GND_18") (pintype "passive"))
      (node (ref "S900") (pin "19") (pinfunction "GND_19") (pintype "passive"))
      (node (ref "S900") (pin "2") (pinfunction "GND_2") (pintype "passive"))
      (node (ref "S900") (pin "4") (pinfunction "GND_4") (pintype "passive"))
      (node (ref "S900") (pin "5") (pinfunction "GND_5") (pintype "passive"))
      (node (ref "S900") (pin "6") (pinfunction "GND_6") (pintype "passive"))
      (node (ref "S900") (pin "7") (pinfunction "GND_7") (pintype "passive"))
      (node (ref "S900") (pin "9") (pinfunction "GND_9") (pintype "passive"))
      (node (ref "S901") (pin "0") (pinfunction "GNDx15_0") (pintype "passive"))
      (node (ref "S901") (pin "1") (pinfunction "GND_1") (pintype "passive"))
      (node (ref "S901") (pin "10") (pinfunction "GND_10") (pintype "passive"))
      (node (ref "S901") (pin "11") (pinfunction "GND_11") (pintype "passive"))
      (node (ref "S901") (pin "12") (pinfunction "GND_12") (pintype "passive"))
      (node (ref "S901") (pin "14") (pinfunction "GND_14") (pintype "passive"))
      (node (ref "S901") (pin "15") (pinfunction "GND_15") (pintype "passive"))
      (node (ref "S901") (pin "18") (pinfunction "GND_18") (pintype "passive"))
      (node (ref "S901") (pin "19") (pinfunction "GND_19") (pintype "passive"))
      (node (ref "S901") (pin "2") (pinfunction "GND_2") (pintype "passive"))
      (node (ref "S901") (pin "4") (pinfunction "GND_4") (pintype "passive"))
      (node (ref "S901") (pin "5") (pinfunction "GND_5") (pintype "passive"))
      (node (ref "S901") (pin "6") (pinfunction "GND_6") (pintype "passive"))
      (node (ref "S901") (pin "7") (pinfunction "GND_7") (pintype "passive"))
      (node (ref "S901") (pin "9") (pinfunction "GND_9") (pintype "passive"))
      (node (ref "U900") (pin "2") (pintype "power_in"))
      (node (ref "U900") (pin "4") (pintype "power_in"))
      (node (ref "U901") (pin "0") (pinfunction "GND_0") (pintype "input"))
      (node (ref "U901") (pin "7") (pinfunction "GND_7") (pintype "input"))
      (node (ref "U902") (pin "2") (pinfunction "V-_2") (pintype "input"))
      (node (ref "U903") (pin "2") (pintype "power_in"))
      (node (ref "U903") (pin "4") (pintype "power_in"))
      (node (ref "U904") (pin "0") (pinfunction "GND_0") (pintype "input"))
      (node (ref "U904") (pin "7") (pinfunction "GND_7") (pintype "input"))
      (node (ref "U905") (pin "2") (pinfunction "V-_2") (pintype "input"))
      (node (ref "Z900") (pin "1") (pinfunction "GND_1") (pintype "input"))
      (node (ref "Z900") (pin "2") (pinfunction "GND_2") (pintype "input"))
      (node (ref "Z901") (pin "2") (pinfunction "GND_2") (pintype "passive"))
      (node (ref "Z902") (pin "1") (pinfunction "GND_1") (pintype "input"))
      (node (ref "Z902") (pin "2") (pinfunction "GND_2") (pintype "input"))
      (node (ref "Z903") (pin "2") (pinfunction "GND_2") (pintype "passive"))
    )
    (net (code "22") (name "Net-(C901-Pad1)") (class "Default")
      (node (ref "C901") (pin "1") (pintype "passive"))
      (node (ref "C903") (pin "2") (pintype "passive"))
      (node (ref "L901") (pin "2") (pinfunction "2_2") (pintype "passive"))
      (node (ref "L902") (pin "2") (pinfunction "2_2") (pintype "passive"))
    )
    (net (code "23") (name "Net-(C905-Pad2)") (class "Default")
      (node (ref "C905") (pin "2") (pintype "passive"))
      (node (ref "R900") (pin "2") (pintype "passive"))
      (node (ref "R903") (pin "2") (pintype "passive"))
    )
    (net (code "24") (name "Net-(C906-Pad1)") (class "Default")
      (node (ref "C906") (pin "1") (pintype "passive"))
      (node (ref "R900") (pin "1") (pintype "passive"))
      (node (ref "R904") (pin "2") (pintype "passive"))
    )
    (net (code "25") (name "Net-(C906-Pad2)") (class "Default")
      (node (ref "C906") (pin "2") (pintype "passive"))
      (node (ref "U900") (pin "1") (pintype "passive"))
    )
    (net (code "26") (name "Net-(C907-Pad1)") (class "Default")
      (node (ref "C907") (pin "1") (pintype "passive"))
      (node (ref "L902") (pin "1") (pinfunction "1_1") (pintype "passive"))
      (node (ref "U900") (pin "3") (pintype "passive"))
    )
    (net (code "27") (name "Net-(C907-Pad2)") (class "Default")
      (node (ref "C907") (pin "2") (pintype "passive"))
      (node (ref "R901") (pin "2") (pintype "passive"))
      (node (ref "R908") (pin "2") (pintype "passive"))
    )
    (net (code "28") (name "Net-(C908-Pad1)") (class "Default")
      (node (ref "C908") (pin "1") (pintype "passive"))
      (node (ref "R902") (pin "1") (pintype "passive"))
      (node (ref "R907") (pin "2") (pintype "passive"))
    )
    (net (code "29") (name "Net-(C909-Pad1)") (class "Default")
      (node (ref "C909") (pin "1") (pintype "passive"))
      (node (ref "L903") (pin "1") (pinfunction "1_1") (pintype "passive"))
      (node (ref "R901") (pin "1") (pintype "passive"))
      (node (ref "R905") (pin "2") (pintype "passive"))
    )
    (net (code "30") (name "Net-(C910-Pad1)") (class "Default")
      (node (ref "C910") (pin "1") (pintype "passive"))
      (node (ref "L903") (pin "2") (pinfunction "2_2") (pintype "passive"))
      (node (ref "L904") (pin "1") (pinfunction "1_1") (pintype "passive"))
    )
    (net (code "31") (name "Net-(C919-Pad1)") (class "Default")
      (node (ref "C919") (pin "1") (pintype "passive"))
      (node (ref "C922") (pin "2") (pintype "passive"))
      (node (ref "L908") (pin "2") (pinfunction "2_2") (pintype "passive"))
      (node (ref "L909") (pin "2") (pinfunction "2_2") (pintype "passive"))
    )
    (net (code "32") (name "Net-(C924-Pad2)") (class "Default")
      (node (ref "C924") (pin "2") (pintype "passive"))
      (node (ref "R915") (pin "2") (pintype "passive"))
      (node (ref "R918") (pin "2") (pintype "passive"))
    )
    (net (code "33") (name "Net-(C925-Pad1)") (class "Default")
      (node (ref "C925") (pin "1") (pintype "passive"))
      (node (ref "R915") (pin "1") (pintype "passive"))
      (node (ref "R919") (pin "2") (pintype "passive"))
    )
    (net (code "34") (name "Net-(C925-Pad2)") (class "Default")
      (node (ref "C925") (pin "2") (pintype "passive"))
      (node (ref "U903") (pin "1") (pintype "passive"))
    )
    (net (code "35") (name "Net-(C926-Pad1)") (class "Default")
      (node (ref "C926") (pin "1") (pintype "passive"))
      (node (ref "L909") (pin "1") (pinfunction "1_1") (pintype "passive"))
      (node (ref "U903") (pin "3") (pintype "passive"))
    )
    (net (code "36") (name "Net-(C926-Pad2)") (class "Default")
      (node (ref "C926") (pin "2") (pintype "passive"))
      (node (ref "R916") (pin "2") (pintype "passive"))
      (node (ref "R923") (pin "2") (pintype "passive"))
    )
    (net (code "37") (name "Net-(C927-Pad1)") (class "Default")
      (node (ref "C927") (pin "1") (pintype "passive"))
      (node (ref "R917") (pin "1") (pintype "passive"))
      (node (ref "R922") (pin "2") (pintype "passive"))
    )
    (net (code "38") (name "Net-(C929-Pad1)") (class "Default")
      (node (ref "C929") (pin "1") (pintype "passive"))
      (node (ref "L910") (pin "1") (pinfunction "1_1") (pintype "passive"))
      (node (ref "R916") (pin "1") (pintype "passive"))
      (node (ref "R920") (pin "2") (pintype "passive"))
    )
    (net (code "39") (name "Net-(C930-Pad1)") (class "Default")
      (node (ref "C930") (pin "1") (pintype "passive"))
      (node (ref "L910") (pin "2") (pinfunction "2_2") (pintype "passive"))
      (node (ref "L911") (pin "1") (pinfunction "1_1") (pintype "passive"))
    )
    (net (code "40") (name "Net-(L905-Pad2)") (class "Default")
      (node (ref "L905") (pin "2") (pinfunction "2_2") (pintype "passive"))
      (node (ref "R911") (pin "1") (pintype "passive"))
    )
    (net (code "41") (name "Net-(L906-Pad2)") (class "Default")
      (node (ref "L906") (pin "2") (pinfunction "2_2") (pintype "passive"))
      (node (ref "R912") (pin "1") (pintype "passive"))
    )
    (net (code "42") (name "Net-(L912-Pad2)") (class "Default")
      (node (ref "L912") (pin "2") (pinfunction "2_2") (pintype "passive"))
      (node (ref "R926") (pin "1") (pintype "passive"))
    )
    (net (code "43") (name "Net-(L913-Pad2)") (class "Default")
      (node (ref "L913") (pin "2") (pinfunction "2_2") (pintype "passive"))
      (node (ref "R927") (pin "1") (pintype "passive"))
    )
    (net (code "44") (name "Net-(S900-COM)") (class "Default")
      (node (ref "C905") (pin "1") (pintype "passive"))
      (node (ref "S900") (pin "8") (pinfunction "COM_8") (pintype "passive"))
      (node (ref "TP901") (pin "1") (pinfunction "1_1") (pintype "passive"))
    )
    (net (code "45") (name "Net-(S900-CTRL1)") (class "Default")
      (node (ref "C916") (pin "2") (pintype "passive"))
      (node (ref "R912") (pin "2") (pintype "passive"))
      (node (ref "S900") (pin "17") (pinfunction "CTRL1_17") (pintype "passive"))
    )
    (net (code "46") (name "Net-(S900-CTRL2)") (class "Default")
      (node (ref "C915") (pin "2") (pintype "passive"))
      (node (ref "R911") (pin "2") (pintype "passive"))
      (node (ref "S900") (pin "16") (pinfunction "CTRL2_16") (pintype "passive"))
    )
    (net (code "47") (name "Net-(S900-Vdd)") (class "Default")
      (node (ref "C900") (pin "2") (pintype "passive"))
      (node (ref "C902") (pin "1") (pintype "passive"))
      (node (ref "L900") (pin "1") (pinfunction "1_1") (pintype "passive"))
      (node (ref "S900") (pin "20") (pinfunction "Vdd_20") (pintype "passive"))
    )
    (net (code "48") (name "Net-(S901-COM)") (class "Default")
      (node (ref "C924") (pin "1") (pintype "passive"))
      (node (ref "S901") (pin "8") (pinfunction "COM_8") (pintype "passive"))
      (node (ref "TP906") (pin "1") (pinfunction "1_1") (pintype "passive"))
    )
    (net (code "49") (name "Net-(S901-CTRL1)") (class "Default")
      (node (ref "C936") (pin "2") (pintype "passive"))
      (node (ref "R927") (pin "2") (pintype "passive"))
      (node (ref "S901") (pin "17") (pinfunction "CTRL1_17") (pintype "passive"))
    )
    (net (code "50") (name "Net-(S901-CTRL2)") (class "Default")
      (node (ref "C935") (pin "2") (pintype "passive"))
      (node (ref "R926") (pin "2") (pintype "passive"))
      (node (ref "S901") (pin "16") (pinfunction "CTRL2_16") (pintype "passive"))
    )
    (net (code "51") (name "Net-(S901-Vdd)") (class "Default")
      (node (ref "C918") (pin "2") (pintype "passive"))
      (node (ref "C921") (pin "1") (pintype "passive"))
      (node (ref "L907") (pin "1") (pinfunction "1_1") (pintype "passive"))
      (node (ref "S901") (pin "20") (pinfunction "Vdd_20") (pintype "passive"))
    )
    (net (code "52") (name "Net-(U901-CAP+)") (class "Default")
      (node (ref "C912") (pin "2") (pintype "passive"))
      (node (ref "U901") (pin "4") (pinfunction "CAP+_4") (pintype "passive"))
    )
    (net (code "53") (name "Net-(U901-CAP-)") (class "Default")
      (node (ref "C912") (pin "1") (pintype "passive"))
      (node (ref "U901") (pin "5") (pinfunction "CAP-_5") (pintype "passive"))
    )
    (net (code "54") (name "Net-(U901-IN+)") (class "Default")
      (node (ref "C914") (pin "2") (pintype "passive"))
      (node (ref "U901") (pin "2") (pinfunction "IN+_2") (pintype "input"))
    )
    (net (code "55") (name "Net-(U901-IN-)") (class "Default")
      (node (ref "C913") (pin "2") (pintype "passive"))
      (node (ref "U901") (pin "3") (pinfunction "IN-_3") (pintype "input"))
    )
    (net (code "56") (name "Net-(U901-OUT)") (class "Default")
      (node (ref "R913") (pin "2") (pintype "passive"))
      (node (ref "U901") (pin "8") (pinfunction "OUT_8") (pintype "output"))
      (node (ref "U902") (pin "3") (pinfunction "IN+_3") (pintype "input"))
    )
    (net (code "57") (name "Net-(U902-IN-)") (class "Default")
      (node (ref "R914") (pin "1") (pintype "passive"))
      (node (ref "TP905") (pin "1") (pinfunction "1_1") (pintype "passive"))
      (node (ref "U902") (pin "1") (pinfunction "OUT_1") (pintype "output"))
      (node (ref "U902") (pin "4") (pinfunction "IN-_4") (pintype "input"))
    )
    (net (code "58") (name "Net-(U904-CAP+)") (class "Default")
      (node (ref "C932") (pin "2") (pintype "passive"))
      (node (ref "U904") (pin "4") (pinfunction "CAP+_4") (pintype "passive"))
    )
    (net (code "59") (name "Net-(U904-CAP-)") (class "Default")
      (node (ref "C932") (pin "1") (pintype "passive"))
      (node (ref "U904") (pin "5") (pinfunction "CAP-_5") (pintype "passive"))
    )
    (net (code "60") (name "Net-(U904-IN+)") (class "Default")
      (node (ref "C934") (pin "2") (pintype "passive"))
      (node (ref "U904") (pin "2") (pinfunction "IN+_2") (pintype "input"))
    )
    (net (code "61") (name "Net-(U904-IN-)") (class "Default")
      (node (ref "C933") (pin "2") (pintype "passive"))
      (node (ref "U904") (pin "3") (pinfunction "IN-_3") (pintype "input"))
    )
    (net (code "62") (name "Net-(U904-OUT)") (class "Default")
      (node (ref "R928") (pin "2") (pintype "passive"))
      (node (ref "U904") (pin "8") (pinfunction "OUT_8") (pintype "output"))
      (node (ref "U905") (pin "3") (pinfunction "IN+_3") (pintype "input"))
    )
    (net (code "63") (name "Net-(U905-IN-)") (class "Default")
      (node (ref "R929") (pin "1") (pintype "passive"))
      (node (ref "TP911") (pin "1") (pinfunction "1_1") (pintype "passive"))
      (node (ref "U905") (pin "1") (pinfunction "OUT_1") (pintype "output"))
      (node (ref "U905") (pin "4") (pinfunction "IN-_4") (pintype "input"))
    )
    (net (code "64") (name "Net-(Z900-SUM_PORT)") (class "Default")
      (node (ref "C904") (pin "2") (pintype "passive"))
      (node (ref "Z900") (pin "6") (pinfunction "SUM_PORT_6") (pintype "passive"))
    )
    (net (code "65") (name "Net-(Z901-50R)") (class "Default")
      (node (ref "R909") (pin "2") (pintype "passive"))
      (node (ref "Z901") (pin "4") (pinfunction "50R_4") (pintype "passive"))
    )
    (net (code "66") (name "Net-(Z901-COUPLED)") (class "Default")
      (node (ref "C914") (pin "1") (pintype "passive"))
      (node (ref "R910") (pin "2") (pintype "passive"))
      (node (ref "RFvia900") (pin "1") (pinfunction "1_1") (pintype "input"))
      (node (ref "RFvia901") (pin "1") (pinfunction "1_1") (pintype "input"))
      (node (ref "TP902") (pin "1") (pinfunction "1_1") (pintype "passive"))
      (node (ref "Z901") (pin "3") (pinfunction "COUPLED_3") (pintype "passive"))
    )
    (net (code "67") (name "Net-(Z901-INPUT)") (class "Default")
      (node (ref "C911") (pin "2") (pintype "passive"))
      (node (ref "L904") (pin "2") (pinfunction "2_2") (pintype "passive"))
      (node (ref "TP900") (pin "1") (pinfunction "1_1") (pintype "passive"))
      (node (ref "Z901") (pin "1") (pinfunction "INPUT_1") (pintype "passive"))
    )
    (net (code "68") (name "Net-(Z901-OUTPUT)") (class "Default")
      (node (ref "R902") (pin "2") (pintype "passive"))
      (node (ref "R906") (pin "2") (pintype "passive"))
      (node (ref "Z901") (pin "6") (pinfunction "OUTPUT_6") (pintype "passive"))
    )
    (net (code "69") (name "Net-(Z902-SUM_PORT)") (class "Default")
      (node (ref "C928") (pin "2") (pintype "passive"))
      (node (ref "Z902") (pin "6") (pinfunction "SUM_PORT_6") (pintype "passive"))
    )
    (net (code "70") (name "Net-(Z903-50R)") (class "Default")
      (node (ref "R924") (pin "2") (pintype "passive"))
      (node (ref "Z903") (pin "4") (pinfunction "50R_4") (pintype "passive"))
    )
    (net (code "71") (name "Net-(Z903-COUPLED)") (class "Default")
      (node (ref "C934") (pin "1") (pintype "passive"))
      (node (ref "R925") (pin "2") (pintype "passive"))
      (node (ref "RFvia902") (pin "1") (pinfunction "1_1") (pintype "input"))
      (node (ref "RFvia903") (pin "1") (pinfunction "1_1") (pintype "input"))
      (node (ref "TP908") (pin "1") (pinfunction "1_1") (pintype "passive"))
      (node (ref "Z903") (pin "3") (pinfunction "COUPLED_3") (pintype "passive"))
    )
    (net (code "72") (name "Net-(Z903-INPUT)") (class "Default")
      (node (ref "C931") (pin "2") (pintype "passive"))
      (node (ref "L911") (pin "2") (pinfunction "2_2") (pintype "passive"))
      (node (ref "TP907") (pin "1") (pinfunction "1_1") (pintype "passive"))
      (node (ref "Z903") (pin "1") (pinfunction "INPUT_1") (pintype "passive"))
    )
    (net (code "73") (name "Net-(Z903-OUTPUT)") (class "Default")
      (node (ref "R917") (pin "2") (pintype "passive"))
      (node (ref "R921") (pin "2") (pintype "passive"))
      (node (ref "Z903") (pin "6") (pinfunction "OUTPUT_6") (pintype "passive"))
    )
    (net (code "74") (name "unconnected-(Z900-NC-Pad5)") (class "Default")
      (node (ref "Z900") (pin "5") (pinfunction "NC_5") (pintype "passive"))
    )
    (net (code "75") (name "unconnected-(Z901-NC-Pad5)") (class "Default")
      (node (ref "Z901") (pin "5") (pinfunction "NC_5") (pintype "passive+no_connect"))
    )
    (net (code "76") (name "unconnected-(Z902-NC-Pad5)") (class "Default")
      (node (ref "Z902") (pin "5") (pinfunction "NC_5") (pintype "passive"))
    )
    (net (code "77") (name "unconnected-(Z903-NC-Pad5)") (class "Default")
      (node (ref "Z903") (pin "5") (pinfunction "NC_5") (pintype "passive+no_connect"))
    )
  )
)
